# IR_Sensor.net
KiCad netlist of a schematic drawn in Altium Designer
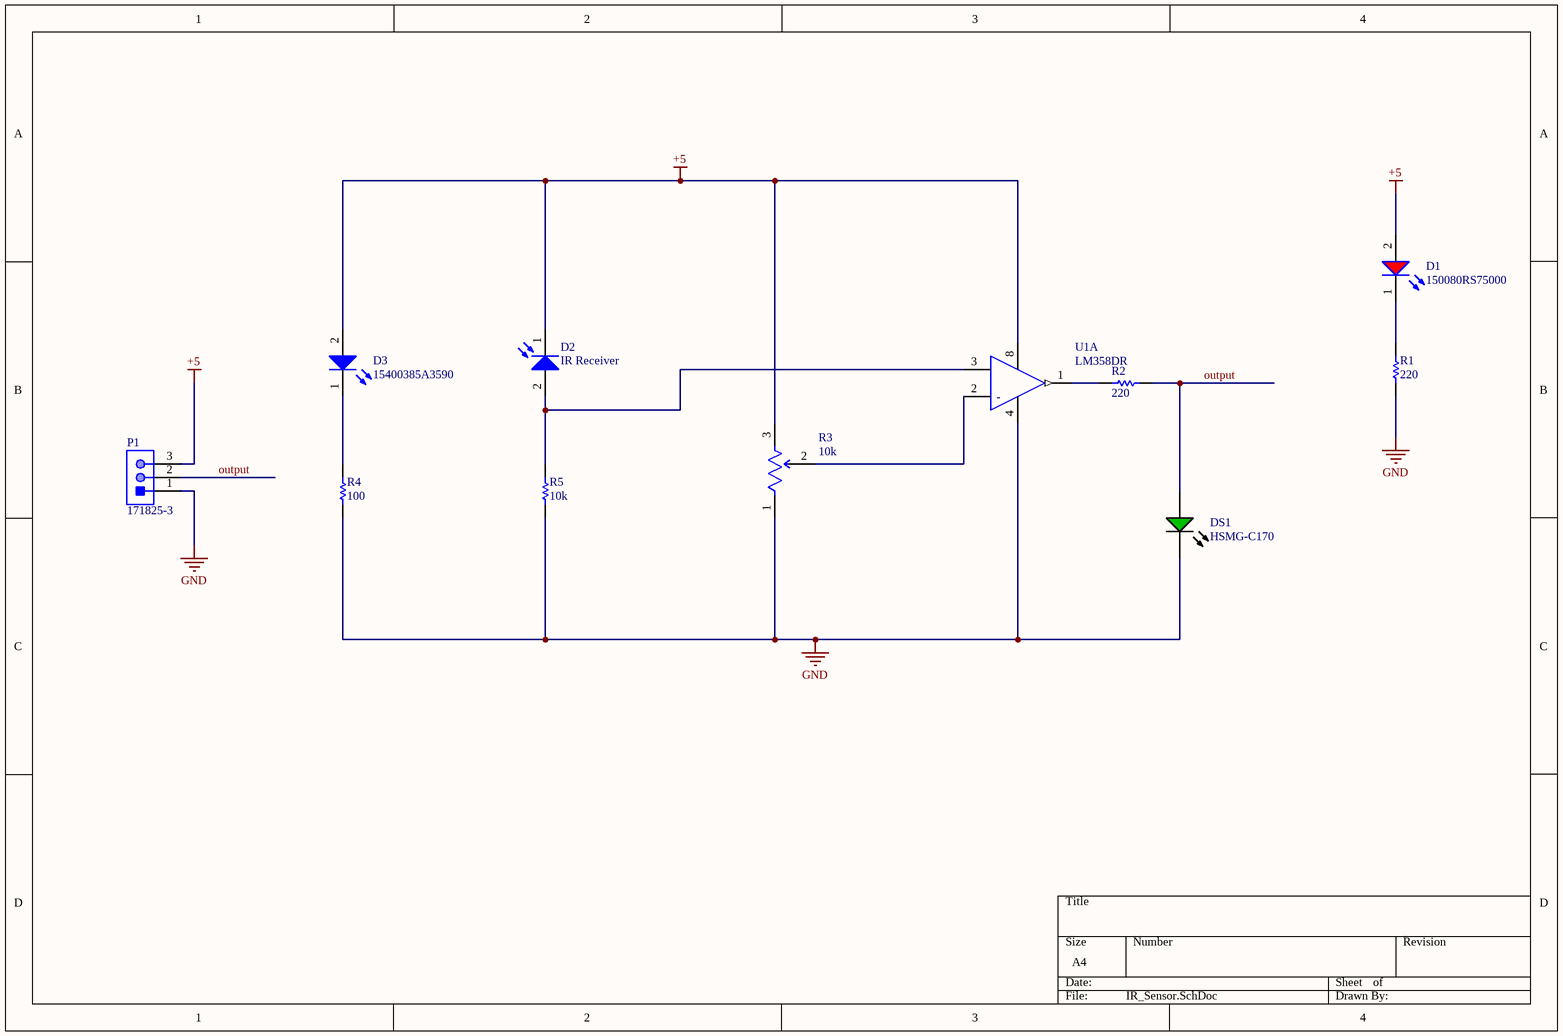
[diagram p0: IR_Sensor.SchDoc]

(export (version "E")
  (design (tool "Eeschema 10.0.6"))
  (components
    (comp (ref "D1")
      (value "150080RS75000")
      (footprint "WL-SMCW_0805_150080xx75000")
      (description "LED Uni-Color Red 630nm 2-Pin Chip 0805(2012Metric) T/R")
      (libsource (lib "Altium Content Vault") (part "LED_Red_2A-1K"))
    )
    (comp (ref "D2")
      (value "IR Receiver")
      (footprint "IR_Receiver")
      (libsource (lib "IR_Sensor") (part "IR_Receiver"))
    )
    (comp (ref "D3")
      (value "15400385A3590")
      (footprint "WL-TIRW_D3.9H5.3")
      (description "15400385A3590 WL-TIRW THT Infrared Round Waterclear")
      (libsource (lib "Altium Content Vault") (part "LED_Infrared_2A-1K"))
    )
    (comp (ref "DS1")
      (value "HSMG-C170")
      (footprint "AVAG-HSMX-C170_V")
      (description "Chip LED, Green, 2.2 V, -40 to 85 degC, 2-Pin SMD, Pb-Free, Tape and Reel")
      (fields (field (name "MANUFACTURER") "Avago"))
      (libsource (lib "Altium Content Vault") (part "LED_GREEN_A1K2-2"))
    )
    (comp (ref "P1")
      (value "171825-3")
      (footprint "TECO-171825-3_V")
      (fields (field (name "MANUFACTURER") "TE Connectivity"))
      (libsource (lib "Altium Content Vault") (part "CN-1P-M-R3"))
    )
    (comp (ref "R1")
      (value "220")
      (footprint "RESC2013X65X40LL15T20")
      (description "Chip Resistor, 0 Ohm, 0.125 W, -55 to 125 degC, 0805 (2012 Metric), RoHS, Tape and Reel")
      (fields (field (name "TOLERANCE") "0%") (field (name "MANUFACTURER") "TE Connectivity"))
      (libsource (lib "Altium Content Vault") (part "RES-2"))
    )
    (comp (ref "R2")
      (value "220")
      (footprint "RESC2013X65X40LL15T20")
      (description "Chip Resistor, 0 Ohm, 0.125 W, -55 to 125 degC, 0805 (2012 Metric), RoHS, Tape and Reel")
      (fields (field (name "TOLERANCE") "0%") (field (name "MANUFACTURER") "TE Connectivity"))
      (libsource (lib "Altium Content Vault") (part "RES-2"))
    )
    (comp (ref "R3")
      (value "10k")
      (footprint "FP-3361P-MFG")
      (description "5 kOhms 0.5W, 1/2W Gull Wing Surface Mount Trimmer Potentiometer Cermet 1 Turn Top Adjustment")
      (fields (field (name "OCTOPART") "https://octopart.com/3361p-1-502glf-bourns-92301"))
      (libsource (lib "Altium Content Vault") (part "2dcfd2547301a7d3209a5e99acfd772"))
    )
    (comp (ref "R4")
      (value "100")
      (footprint "RESC2013X65X40LL15T20")
      (description "Chip Resistor, 0 Ohm, 0.125 W, -55 to 125 degC, 0805 (2012 Metric), RoHS, Tape and Reel")
      (fields (field (name "TOLERANCE") "0%") (field (name "MANUFACTURER") "TE Connectivity"))
      (libsource (lib "Altium Content Vault") (part "RES-2"))
    )
    (comp (ref "R5")
      (value "10k")
      (footprint "RESC2013X65X40LL15T20")
      (description "Chip Resistor, 0 Ohm, 0.125 W, -55 to 125 degC, 0805 (2012 Metric), RoHS, Tape and Reel")
      (fields (field (name "TOLERANCE") "0%") (field (name "MANUFACTURER") "TE Connectivity"))
      (libsource (lib "Altium Content Vault") (part "RES-2"))
    )
    (comp (ref "U1")
      (value "LM358DR")
      (footprint "FP-D0008A-MFG")
      (description "IC OPAMP GP 2 CIRCUIT 8SOIC")
      (libsource (lib "Altium Content Vault") (part "0afdfe5f461d2cdd85604ff8654be97"))
    )
  )
  (nets
    (net (code "1") (name "+5") (class "Default")
      (node (ref "D1") (pin "2") (pinfunction "A_2") (pintype "passive"))
      (node (ref "D2") (pin "1") (pinfunction "K_1") (pintype "passive"))
      (node (ref "D3") (pin "2") (pinfunction "A_2") (pintype "passive"))
      (node (ref "P1") (pin "3") (pinfunction "3_3") (pintype "passive"))
      (node (ref "R3") (pin "3") (pinfunction "CW_3") (pintype "passive"))
      (node (ref "U1") (pin "8") (pinfunction "V+_8") (pintype "power_in"))
    )
    (net (code "2") (name "/output") (class "Default")
      (node (ref "DS1") (pin "1") (pinfunction "A_1") (pintype "passive"))
      (node (ref "P1") (pin "2") (pinfunction "2_2") (pintype "passive"))
      (node (ref "R2") (pin "1") (pinfunction "1_1") (pintype "passive"))
    )
    (net (code "3") (name "GND") (class "Default")
      (node (ref "DS1") (pin "2") (pinfunction "K_2") (pintype "passive"))
      (node (ref "P1") (pin "1") (pinfunction "1_1") (pintype "passive"))
      (node (ref "R1") (pin "1") (pinfunction "1_1") (pintype "passive"))
      (node (ref "R3") (pin "1") (pinfunction "CCW_1") (pintype "passive"))
      (node (ref "R4") (pin "1") (pinfunction "1_1") (pintype "passive"))
      (node (ref "R5") (pin "1") (pinfunction "1_1") (pintype "passive"))
      (node (ref "U1") (pin "4") (pinfunction "V-_4") (pintype "power_in"))
    )
    (net (code "4") (name "Net-(D1-K)") (class "Default")
      (node (ref "D1") (pin "1") (pinfunction "K_1") (pintype "passive"))
      (node (ref "R1") (pin "2") (pinfunction "2_2") (pintype "passive"))
    )
    (net (code "5") (name "Net-(D2-A)") (class "Default")
      (node (ref "D2") (pin "2") (pinfunction "A_2") (pintype "passive"))
      (node (ref "R5") (pin "2") (pinfunction "2_2") (pintype "passive"))
      (node (ref "U1") (pin "3") (pinfunction "IN1+_3") (pintype "tri_state"))
    )
    (net (code "6") (name "Net-(D3-K)") (class "Default")
      (node (ref "D3") (pin "1") (pinfunction "K_1") (pintype "passive"))
      (node (ref "R4") (pin "2") (pinfunction "2_2") (pintype "passive"))
    )
    (net (code "7") (name "Net-(R3-WIPER)") (class "Default")
      (node (ref "R3") (pin "2") (pinfunction "WIPER_2") (pintype "passive"))
      (node (ref "U1") (pin "2") (pinfunction "IN1-_2") (pintype "tri_state"))
    )
    (net (code "8") (name "Net-(U1A-1OUT)") (class "Default")
      (node (ref "R2") (pin "2") (pinfunction "2_2") (pintype "passive"))
      (node (ref "U1") (pin "1") (pinfunction "1OUT_1") (pintype "output"))
    )
  )
)
